# motorEncoder.net
KiCad netlist of a schematic drawn in Altium Designer
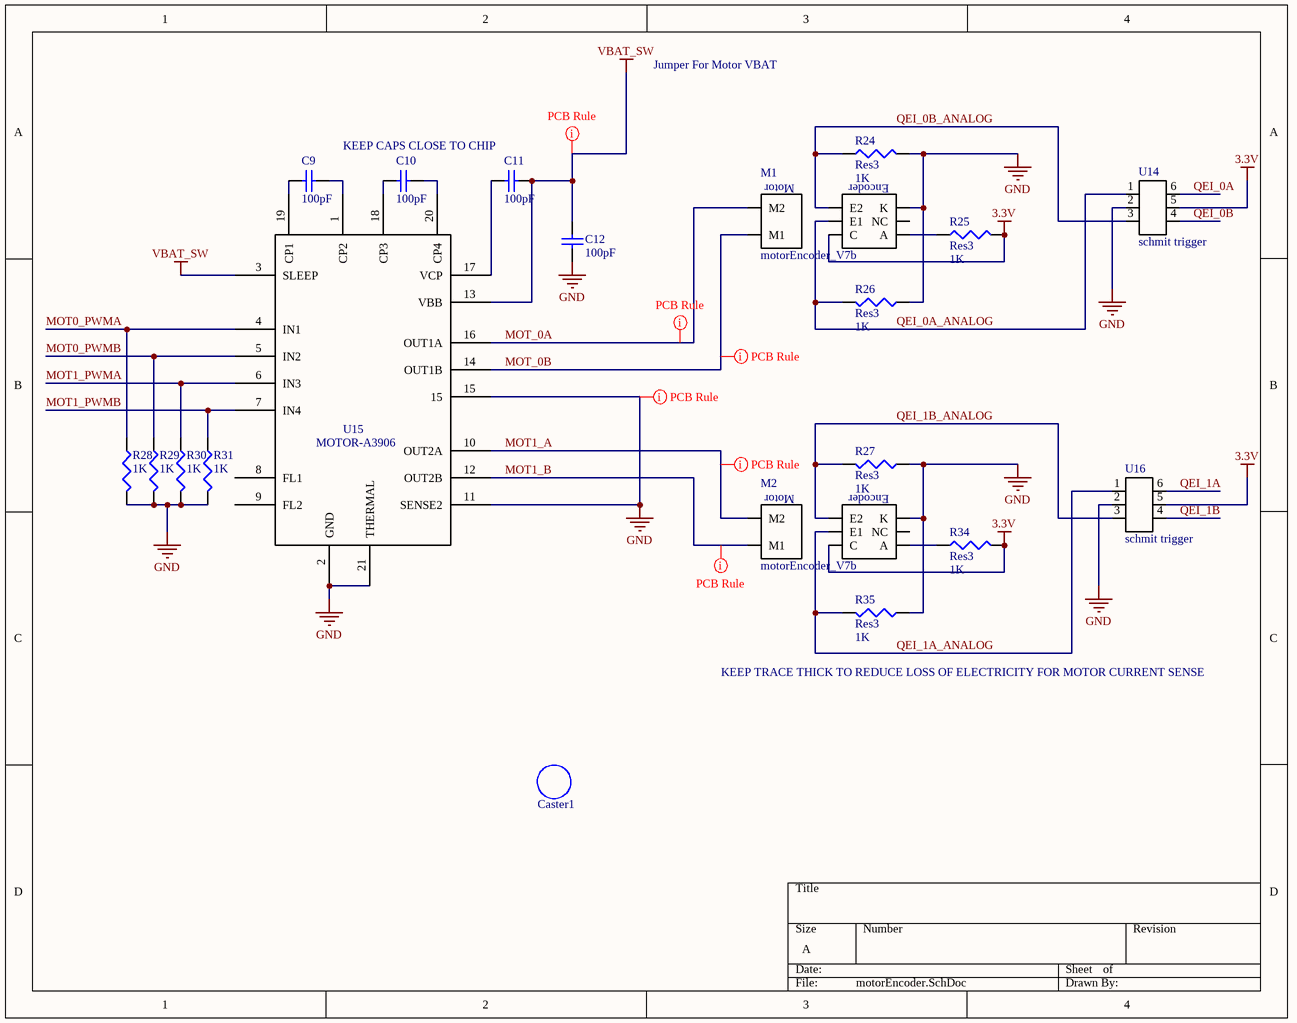
[diagram p0: motorEncoder.SchDoc]

(export (version "E")
  (design (tool "Eeschema 10.0.6"))
  (components
    (comp (ref "C9")
      (value "100pF")
      (footprint "CAPC1005L")
      (description "Capacitor (Semiconductor SIM Model)")
      (fields (field (name "Comment") "Cap Semi") (field (name "PUBLISHER") "Altium Limited"))
      (libsource (lib "Miscellaneous Devices") (part "Cap Semi"))
    )
    (comp (ref "C10")
      (value "100pF")
      (footprint "CAPC1005L")
      (description "Capacitor (Semiconductor SIM Model)")
      (fields (field (name "Comment") "Cap Semi") (field (name "PUBLISHER") "Altium Limited"))
      (libsource (lib "Miscellaneous Devices") (part "Cap Semi"))
    )
    (comp (ref "C11")
      (value "100pF")
      (footprint "CAPC1005L")
      (description "Capacitor (Semiconductor SIM Model)")
      (fields (field (name "Comment") "Cap Semi") (field (name "PUBLISHER") "Altium Limited"))
      (libsource (lib "Miscellaneous Devices") (part "Cap Semi"))
    )
    (comp (ref "C12")
      (value "100pF")
      (footprint "CAPC1005L")
      (description "Capacitor (Semiconductor SIM Model)")
      (fields (field (name "Comment") "Cap Semi") (field (name "PUBLISHER") "Altium Limited"))
      (libsource (lib "Miscellaneous Devices") (part "Cap Semi"))
    )
    (comp (ref "Caster1")
      (value "non connect")
      (footprint "3/4\"CASTER2")
      (description "This is just a space saver to get the caster onto the pcb")
      (libsource (lib "mrone") (part "Caster 3/4in"))
    )
    (comp (ref "M1")
      (value "motorEncoder_V7b")
      (footprint "motorEncoder_V7b")
      (libsource (lib "mrone") (part "motorEncoder_V7b"))
    )
    (comp (ref "M2")
      (value "motorEncoder_V7b")
      (footprint "motorEncoder_V7b")
      (libsource (lib "mrone") (part "motorEncoder_V7b"))
    )
    (comp (ref "R24")
      (value "Res3")
      (footprint "RESC1608L")
      (description "Resistor")
      (fields (field (name "ALTIUM_VALUE") "1K") (field (name "PUBLISHER") "Altium Limited"))
      (libsource (lib "Miscellaneous Devices") (part "Res3"))
    )
    (comp (ref "R25")
      (value "Res3")
      (footprint "RESC1608L")
      (description "Resistor")
      (fields (field (name "ALTIUM_VALUE") "1K") (field (name "PUBLISHER") "Altium Limited"))
      (libsource (lib "Miscellaneous Devices") (part "Res3"))
    )
    (comp (ref "R26")
      (value "Res3")
      (footprint "RESC1608L")
      (description "Resistor")
      (fields (field (name "ALTIUM_VALUE") "1K") (field (name "PUBLISHER") "Altium Limited"))
      (libsource (lib "Miscellaneous Devices") (part "Res3"))
    )
    (comp (ref "R27")
      (value "Res3")
      (footprint "RESC1608L")
      (description "Resistor")
      (fields (field (name "ALTIUM_VALUE") "1K") (field (name "PUBLISHER") "Altium Limited"))
      (libsource (lib "Miscellaneous Devices") (part "Res3"))
    )
    (comp (ref "R28")
      (value "1K")
      (footprint "RESC1608L")
      (description "Resistor")
      (fields (field (name "Comment") "Res3") (field (name "PUBLISHER") "Altium Limited"))
      (libsource (lib "Miscellaneous Devices") (part "Res3"))
    )
    (comp (ref "R29")
      (value "1K")
      (footprint "RESC1608L")
      (description "Resistor")
      (fields (field (name "Comment") "Res3") (field (name "PUBLISHER") "Altium Limited"))
      (libsource (lib "Miscellaneous Devices") (part "Res3"))
    )
    (comp (ref "R30")
      (value "1K")
      (footprint "RESC1608L")
      (description "Resistor")
      (fields (field (name "Comment") "Res3") (field (name "PUBLISHER") "Altium Limited"))
      (libsource (lib "Miscellaneous Devices") (part "Res3"))
    )
    (comp (ref "R31")
      (value "1K")
      (footprint "RESC1608L")
      (description "Resistor")
      (fields (field (name "Comment") "Res3") (field (name "PUBLISHER") "Altium Limited"))
      (libsource (lib "Miscellaneous Devices") (part "Res3"))
    )
    (comp (ref "R34")
      (value "Res3")
      (footprint "RESC1608L")
      (description "Resistor")
      (fields (field (name "ALTIUM_VALUE") "1K") (field (name "PUBLISHER") "Altium Limited"))
      (libsource (lib "Miscellaneous Devices") (part "Res3"))
    )
    (comp (ref "R35")
      (value "Res3")
      (footprint "RESC1608L")
      (description "Resistor")
      (fields (field (name "ALTIUM_VALUE") "1K") (field (name "PUBLISHER") "Altium Limited"))
      (libsource (lib "Miscellaneous Devices") (part "Res3"))
    )
    (comp (ref "U14")
      (value "schmit trigger")
      (footprint "DCK(R-PDSO-C6)")
      (libsource (lib "mrone") (part "schmit trigger"))
    )
    (comp (ref "U15")
      (value "MOTOR-A3906")
      (footprint "QFN-20")
      (libsource (lib "V2_altium") (part "MOTOR-A3906"))
    )
    (comp (ref "U16")
      (value "schmit trigger")
      (footprint "DCK(R-PDSO-C6)")
      (libsource (lib "mrone") (part "schmit trigger"))
    )
  )
  (nets
    (net (code "2") (name "/MOT0_PWMA") (class "Default")
      (node (ref "R28") (pin "1") (pinfunction "1_1") (pintype "passive"))
      (node (ref "U15") (pin "4") (pinfunction "IN1_4") (pintype "passive"))
    )
    (net (code "3") (name "/MOT0_PWMB") (class "Default")
      (node (ref "R29") (pin "1") (pinfunction "1_1") (pintype "passive"))
      (node (ref "U15") (pin "5") (pinfunction "IN2_5") (pintype "passive"))
    )
    (net (code "4") (name "/MOT1_A") (class "Default")
      (node (ref "M2") (pin "M2") (pinfunction "M2_M2") (pintype "passive"))
      (node (ref "U15") (pin "10") (pinfunction "OUT2A_10") (pintype "passive"))
    )
    (net (code "5") (name "/MOT1_B") (class "Default")
      (node (ref "M2") (pin "M1") (pinfunction "M1_M1") (pintype "passive"))
      (node (ref "U15") (pin "12") (pinfunction "OUT2B_12") (pintype "passive"))
    )
    (net (code "6") (name "/MOT1_PWMA") (class "Default")
      (node (ref "R30") (pin "1") (pinfunction "1_1") (pintype "passive"))
      (node (ref "U15") (pin "6") (pinfunction "IN3_6") (pintype "passive"))
    )
    (net (code "7") (name "/MOT1_PWMB") (class "Default")
      (node (ref "R31") (pin "1") (pinfunction "1_1") (pintype "passive"))
      (node (ref "U15") (pin "7") (pinfunction "IN4_7") (pintype "passive"))
    )
    (net (code "8") (name "/MOT_0A") (class "Default")
      (node (ref "M1") (pin "M2") (pinfunction "M2_M2") (pintype "passive"))
      (node (ref "U15") (pin "16") (pinfunction "OUT1A_16") (pintype "passive"))
    )
    (net (code "9") (name "/MOT_0B") (class "Default")
      (node (ref "M1") (pin "M1") (pinfunction "M1_M1") (pintype "passive"))
      (node (ref "U15") (pin "14") (pinfunction "OUT1B_14") (pintype "passive"))
    )
    (net (code "10") (name "/QEI_0A") (class "Default")
      (node (ref "U14") (pin "6") (pinfunction "4_6") (pintype "passive"))
    )
    (net (code "11") (name "/QEI_0A_ANALOG") (class "Default")
      (node (ref "M1") (pin "E1") (pinfunction "E1_E1") (pintype "passive"))
      (node (ref "R26") (pin "2") (pinfunction "2_2") (pintype "passive"))
      (node (ref "U14") (pin "1") (pinfunction "1_1") (pintype "passive"))
    )
    (net (code "12") (name "/QEI_0B") (class "Default")
      (node (ref "U14") (pin "4") (pinfunction "4_4") (pintype "passive"))
    )
    (net (code "13") (name "/QEI_0B_ANALOG") (class "Default")
      (node (ref "M1") (pin "E2") (pinfunction "E2_E2") (pintype "passive"))
      (node (ref "R24") (pin "1") (pinfunction "1_1") (pintype "passive"))
      (node (ref "U14") (pin "3") (pinfunction "3_3") (pintype "passive"))
    )
    (net (code "14") (name "/QEI_1A") (class "Default")
      (node (ref "U16") (pin "6") (pinfunction "4_6") (pintype "passive"))
    )
    (net (code "15") (name "/QEI_1A_ANALOG") (class "Default")
      (node (ref "M2") (pin "E1") (pinfunction "E1_E1") (pintype "passive"))
      (node (ref "R35") (pin "2") (pinfunction "2_2") (pintype "passive"))
      (node (ref "U16") (pin "1") (pinfunction "1_1") (pintype "passive"))
    )
    (net (code "16") (name "/QEI_1B") (class "Default")
      (node (ref "U16") (pin "4") (pinfunction "4_4") (pintype "passive"))
    )
    (net (code "17") (name "/QEI_1B_ANALOG") (class "Default")
      (node (ref "M2") (pin "E2") (pinfunction "E2_E2") (pintype "passive"))
      (node (ref "R27") (pin "2") (pinfunction "2_2") (pintype "passive"))
      (node (ref "U16") (pin "3") (pinfunction "3_3") (pintype "passive"))
    )
    (net (code "18") (name "3.3V") (class "Default")
      (node (ref "M1") (pin "C") (pinfunction "C_C") (pintype "passive"))
      (node (ref "M2") (pin "C") (pinfunction "C_C") (pintype "passive"))
      (node (ref "R25") (pin "2") (pinfunction "2_2") (pintype "passive"))
      (node (ref "R34") (pin "2") (pinfunction "2_2") (pintype "passive"))
      (node (ref "U14") (pin "5") (pinfunction "5_5") (pintype "passive"))
      (node (ref "U16") (pin "5") (pinfunction "5_5") (pintype "passive"))
    )
    (net (code "19") (name "GND") (class "Default")
      (node (ref "C12") (pin "1") (pinfunction "1_1") (pintype "passive"))
      (node (ref "M1") (pin "K") (pinfunction "K_K") (pintype "passive"))
      (node (ref "M2") (pin "K") (pinfunction "K_K") (pintype "passive"))
      (node (ref "R24") (pin "2") (pinfunction "2_2") (pintype "passive"))
      (node (ref "R26") (pin "1") (pinfunction "1_1") (pintype "passive"))
      (node (ref "R27") (pin "1") (pinfunction "1_1") (pintype "passive"))
      (node (ref "R28") (pin "2") (pinfunction "2_2") (pintype "passive"))
      (node (ref "R29") (pin "2") (pinfunction "2_2") (pintype "passive"))
      (node (ref "R30") (pin "2") (pinfunction "2_2") (pintype "passive"))
      (node (ref "R31") (pin "2") (pinfunction "2_2") (pintype "passive"))
      (node (ref "R35") (pin "1") (pinfunction "1_1") (pintype "passive"))
      (node (ref "U14") (pin "2") (pinfunction "2_2") (pintype "passive"))
      (node (ref "U15") (pin "11") (pinfunction "SENSE2_11") (pintype "passive"))
      (node (ref "U15") (pin "15") (pinfunction "15_15") (pintype "passive"))
      (node (ref "U15") (pin "2") (pinfunction "GND_2") (pintype "passive"))
      (node (ref "U15") (pin "21") (pinfunction "THERMAL_21") (pintype "passive"))
      (node (ref "U16") (pin "2") (pinfunction "2_2") (pintype "passive"))
    )
    (net (code "20") (name "Net-(M1-PadA)") (class "Default")
      (node (ref "M1") (pin "A") (pinfunction "A_A") (pintype "passive"))
      (node (ref "R25") (pin "1") (pinfunction "1_1") (pintype "passive"))
    )
    (net (code "21") (name "Net-(M2-PadA)") (class "Default")
      (node (ref "M2") (pin "A") (pinfunction "A_A") (pintype "passive"))
      (node (ref "R34") (pin "1") (pinfunction "1_1") (pintype "passive"))
    )
    (net (code "22") (name "Net-(U15-CP1)") (class "Default")
      (node (ref "C9") (pin "1") (pinfunction "1_1") (pintype "passive"))
      (node (ref "U15") (pin "19") (pinfunction "CP1_19") (pintype "passive"))
    )
    (net (code "23") (name "Net-(U15-CP2)") (class "Default")
      (node (ref "C9") (pin "2") (pinfunction "2_2") (pintype "passive"))
      (node (ref "U15") (pin "1") (pinfunction "CP2_1") (pintype "passive"))
    )
    (net (code "24") (name "Net-(U15-CP3)") (class "Default")
      (node (ref "C10") (pin "1") (pinfunction "1_1") (pintype "passive"))
      (node (ref "U15") (pin "18") (pinfunction "CP3_18") (pintype "passive"))
    )
    (net (code "25") (name "Net-(U15-CP4)") (class "Default")
      (node (ref "C10") (pin "2") (pinfunction "2_2") (pintype "passive"))
      (node (ref "U15") (pin "20") (pinfunction "CP4_20") (pintype "passive"))
    )
    (net (code "26") (name "Net-(U15-VCP)") (class "Default")
      (node (ref "C11") (pin "2") (pinfunction "2_2") (pintype "passive"))
      (node (ref "U15") (pin "17") (pinfunction "VCP_17") (pintype "passive"))
    )
    (net (code "27") (name "VBAT_SW") (class "Default")
      (node (ref "C11") (pin "1") (pinfunction "1_1") (pintype "passive"))
      (node (ref "C12") (pin "2") (pinfunction "2_2") (pintype "passive"))
      (node (ref "U15") (pin "13") (pinfunction "VBB_13") (pintype "passive"))
      (node (ref "U15") (pin "3") (pinfunction "SLEEP_3") (pintype "passive"))
    )
    (net (code "28") (name "unconnected-(M1-PadNC)") (class "Default")
      (node (ref "M1") (pin "NC") (pinfunction "NC_NC") (pintype "passive"))
    )
    (net (code "29") (name "unconnected-(M2-PadNC)") (class "Default")
      (node (ref "M2") (pin "NC") (pinfunction "NC_NC") (pintype "passive"))
    )
    (net (code "30") (name "unconnected-(U15-FL1-Pad8)") (class "Default")
      (node (ref "U15") (pin "8") (pinfunction "FL1_8") (pintype "passive"))
    )
    (net (code "31") (name "unconnected-(U15-FL2-Pad9)") (class "Default")
      (node (ref "U15") (pin "9") (pinfunction "FL2_9") (pintype "passive"))
    )
  )
)
